# Controlador_de_velocidad_-_Placa_fuente.net
KiCad netlist of a schematic drawn in Altium Designer
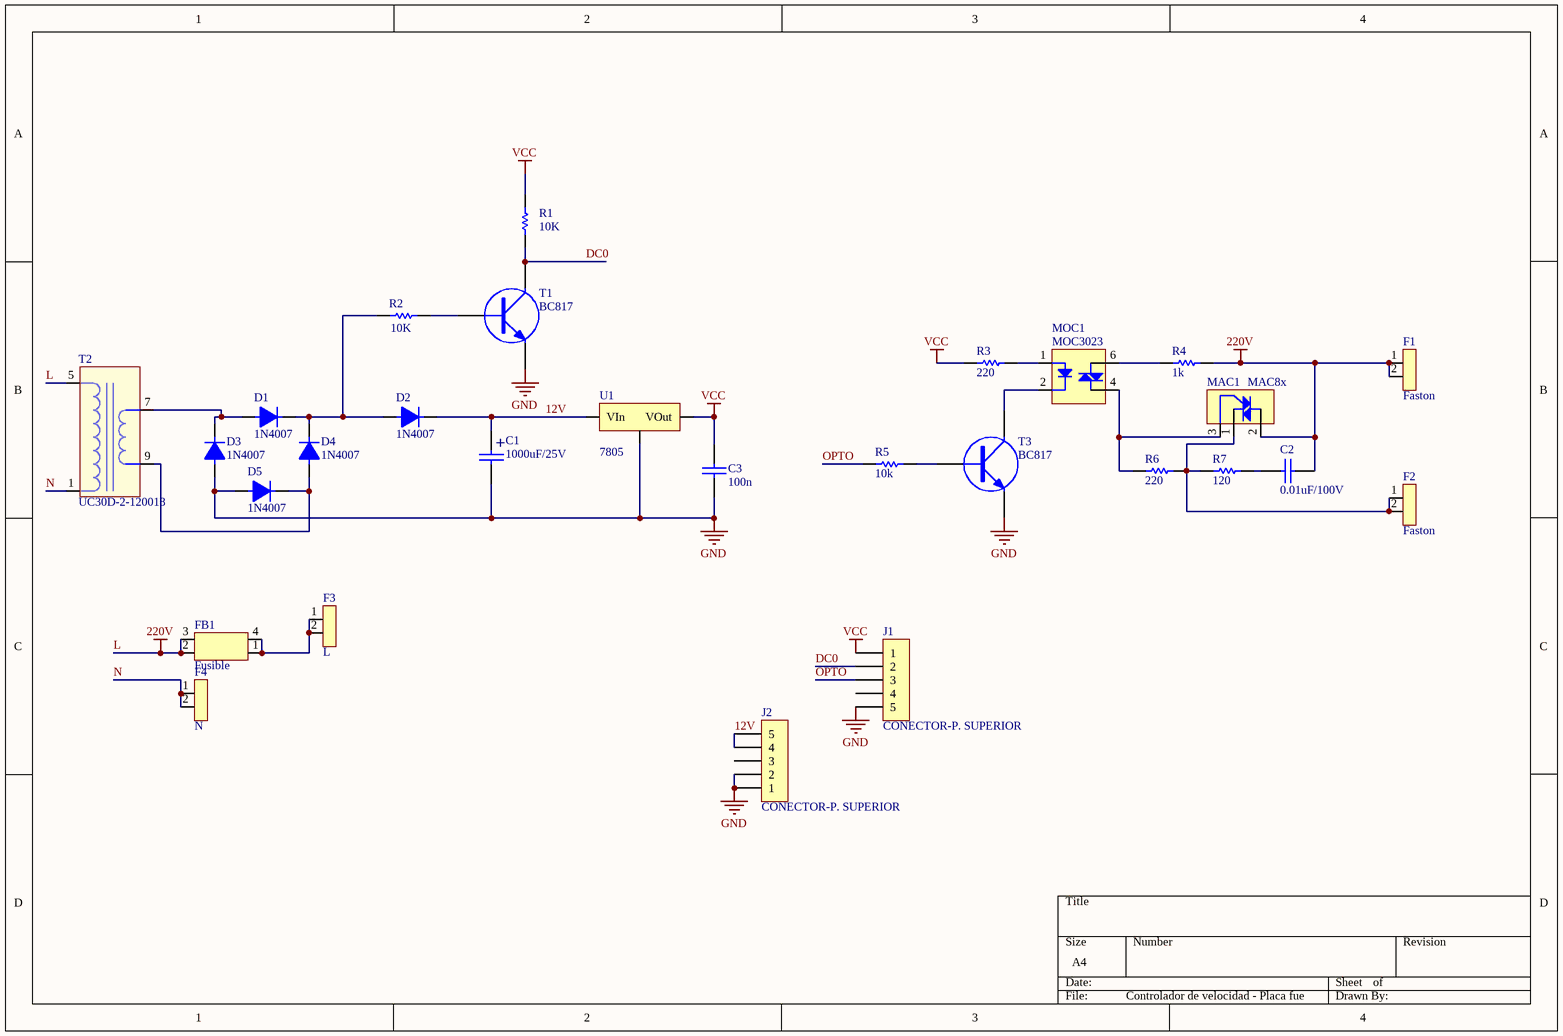
[diagram p0: Controlador de velocidad - Placa fuente.SchDoc]

(export (version "E")
  (design (tool "Eeschema 10.0.6"))
  (components
    (comp (ref "C1") (value "1000uF/25V") (footprint "CAP300RP") (libsource (lib "LIBPIOIX") (part "CAPPOL")))
    (comp (ref "C2") (value "0.01uF/100V") (footprint "CAP200") (libsource (lib "LIBPIOIX") (part "CAP")))
    (comp (ref "C3") (value "100n") (footprint "CAP200") (libsource (lib "LIBPIOIX") (part "CAP")))
    (comp (ref "D1") (value "1N4007") (footprint "DO41") (libsource (lib "LIBPIOIX") (part "DIODO")))
    (comp (ref "D2") (value "1N4007") (footprint "DO41") (libsource (lib "LIBPIOIX") (part "DIODO")))
    (comp (ref "D3") (value "1N4007") (footprint "DO41") (libsource (lib "LIBPIOIX") (part "DIODO")))
    (comp (ref "D4") (value "1N4007") (footprint "DO41") (libsource (lib "LIBPIOIX") (part "DIODO")))
    (comp (ref "D5") (value "1N4007") (footprint "DO41") (libsource (lib "LIBPIOIX") (part "DIODO")))
    (comp (ref "F1")
      (value "Faston")
      (footprint "Faston_V")
      (libsource (lib "Integrated_Library1") (part "FastonX1"))
    )
    (comp (ref "F2")
      (value "Faston")
      (footprint "Faston_V")
      (libsource (lib "Integrated_Library1") (part "FastonX1"))
    )
    (comp (ref "F3")
      (value "L")
      (footprint "Faston_V")
      (libsource (lib "Integrated_Library1") (part "FastonX1"))
    )
    (comp (ref "F4")
      (value "N")
      (footprint "Faston_V")
      (libsource (lib "Integrated_Library1") (part "FastonX1"))
    )
    (comp (ref "FB1")
      (value "Fusible")
      (footprint "Porta_fuse_2")
      (libsource (lib "Integrated_Library1") (part "Porta_fuse_1"))
    )
    (comp (ref "J1")
      (value "CONECTOR-P. SUPERIOR")
      (footprint "SIP5")
      (libsource (lib "LIBEBAL") (part "CON5"))
    )
    (comp (ref "J2") (value "CONECTOR-P. SUPERIOR") (footprint "SIP5") (libsource (lib "") (part "CON5_1")))
    (comp (ref "MAC1")
      (value "MAC8x")
      (footprint "TO-220_vert")
      (libsource (lib "Integrated_Library1") (part "MAC8x"))
    )
    (comp (ref "MOC1")
      (value "MOC3023")
      (footprint "4N33")
      (libsource (lib "Integrated_Library1") (part "MOC3023"))
    )
    (comp (ref "R1") (value "10K") (footprint "0805") (libsource (lib "LIBPIOIX") (part "RES")))
    (comp (ref "R2") (value "10K") (footprint "0805") (libsource (lib "LIBPIOIX") (part "RES")))
    (comp (ref "R3") (value "220") (footprint "0805") (libsource (lib "LIBPIOIX") (part "RES")))
    (comp (ref "R4") (value "1k") (footprint "RES300") (libsource (lib "LIBPIOIX") (part "RES")))
    (comp (ref "R5") (value "10k") (footprint "0805") (libsource (lib "LIBPIOIX") (part "RES")))
    (comp (ref "R6") (value "220") (footprint "RES300") (libsource (lib "LIBPIOIX") (part "RES")))
    (comp (ref "R7") (value "120") (footprint "RES400") (libsource (lib "LIBPIOIX") (part "RES")))
    (comp (ref "T1") (value "BC817") (footprint "SOT23") (libsource (lib "LIBPIOIX") (part "TRANSISTOR NPN")))
    (comp (ref "T2")
      (value "UC30D-2-120018")
      (footprint "Trafo_220_12_1")
      (libsource (lib "Integrated_Lib_1") (part "TRAFO_220_12_1"))
    )
    (comp (ref "T3") (value "BC817") (footprint "SOT23") (libsource (lib "LIBPIOIX") (part "TRANSISTOR NPN")))
    (comp (ref "U1")
      (value "7805")
      (footprint "TO-220 H")
      (description "REGULDOR POSITIVO")
      (libsource (lib "LIBPIOIX") (part "78XX"))
    )
  )
  (nets
    (net (code "1") (name "/12V") (class "Default")
      (node (ref "C1") (pin "1") (pinfunction "1_1") (pintype "passive"))
      (node (ref "D2") (pin "2") (pinfunction "2_2") (pintype "passive"))
      (node (ref "J2") (pin "4") (pinfunction "4_4") (pintype "passive"))
      (node (ref "J2") (pin "5") (pinfunction "5_5") (pintype "passive"))
      (node (ref "U1") (pin "1") (pinfunction "VIn_1") (pintype "passive"))
    )
    (net (code "2") (name "/DC0") (class "Default")
      (node (ref "J1") (pin "2") (pinfunction "2_2") (pintype "passive"))
      (node (ref "R1") (pin "1") (pinfunction "1_1") (pintype "passive"))
      (node (ref "T1") (pin "2") (pinfunction "C_2") (pintype "passive"))
    )
    (net (code "3") (name "/N") (class "Default")
      (node (ref "F4") (pin "1") (pintype "power_in"))
      (node (ref "F4") (pin "2") (pintype "power_in"))
      (node (ref "T2") (pin "1") (pinfunction "1_1") (pintype "passive"))
    )
    (net (code "4") (name "/OPTO") (class "Default")
      (node (ref "J1") (pin "3") (pinfunction "3_3") (pintype "passive"))
      (node (ref "R5") (pin "1") (pinfunction "1_1") (pintype "passive"))
    )
    (net (code "5") (name "220V") (class "Default")
      (node (ref "C2") (pin "1") (pinfunction "1_1") (pintype "passive"))
      (node (ref "F1") (pin "1") (pintype "power_in"))
      (node (ref "F1") (pin "2") (pintype "power_in"))
      (node (ref "FB1") (pin "2") (pintype "power_in"))
      (node (ref "FB1") (pin "3") (pintype "power_in"))
      (node (ref "MAC1") (pin "2") (pinfunction "MT2_2") (pintype "passive"))
      (node (ref "R4") (pin "1") (pinfunction "1_1") (pintype "passive"))
      (node (ref "T2") (pin "5") (pinfunction "5_5") (pintype "passive"))
    )
    (net (code "6") (name "GND") (class "Default")
      (node (ref "C1") (pin "2") (pinfunction "2_2") (pintype "passive"))
      (node (ref "C3") (pin "1") (pinfunction "1_1") (pintype "passive"))
      (node (ref "D3") (pin "1") (pinfunction "1_1") (pintype "passive"))
      (node (ref "D5") (pin "1") (pinfunction "1_1") (pintype "passive"))
      (node (ref "J1") (pin "5") (pinfunction "5_5") (pintype "passive"))
      (node (ref "J2") (pin "1") (pinfunction "1_1") (pintype "passive"))
      (node (ref "J2") (pin "2") (pinfunction "2_2") (pintype "passive"))
      (node (ref "T1") (pin "3") (pinfunction "E_3") (pintype "passive"))
      (node (ref "T3") (pin "3") (pinfunction "E_3") (pintype "passive"))
      (node (ref "U1") (pin "2") (pinfunction "GND_2") (pintype "passive"))
    )
    (net (code "7") (name "Net-(C2-Pad2)") (class "Default")
      (node (ref "C2") (pin "2") (pinfunction "2_2") (pintype "passive"))
      (node (ref "R7") (pin "1") (pinfunction "1_1") (pintype "passive"))
    )
    (net (code "8") (name "Net-(D1-Pad1)") (class "Default")
      (node (ref "D1") (pin "1") (pinfunction "1_1") (pintype "passive"))
      (node (ref "D3") (pin "2") (pinfunction "2_2") (pintype "passive"))
      (node (ref "T2") (pin "7") (pinfunction "7_7") (pintype "passive"))
    )
    (net (code "9") (name "Net-(D1-Pad2)") (class "Default")
      (node (ref "D1") (pin "2") (pinfunction "2_2") (pintype "passive"))
      (node (ref "D2") (pin "1") (pinfunction "1_1") (pintype "passive"))
      (node (ref "D4") (pin "2") (pinfunction "2_2") (pintype "passive"))
      (node (ref "R2") (pin "1") (pinfunction "1_1") (pintype "passive"))
    )
    (net (code "10") (name "Net-(D4-Pad1)") (class "Default")
      (node (ref "D4") (pin "1") (pinfunction "1_1") (pintype "passive"))
      (node (ref "D5") (pin "2") (pinfunction "2_2") (pintype "passive"))
      (node (ref "T2") (pin "9") (pinfunction "9_9") (pintype "passive"))
    )
    (net (code "11") (name "Net-(F3-Pad1)") (class "Default")
      (node (ref "F3") (pin "1") (pintype "power_in"))
      (node (ref "F3") (pin "2") (pintype "power_in"))
      (node (ref "FB1") (pin "1") (pintype "power_in"))
      (node (ref "FB1") (pin "4") (pintype "power_in"))
    )
    (net (code "12") (name "Net-(MAC1-G)") (class "Default")
      (node (ref "MAC1") (pin "3") (pinfunction "G_3") (pintype "passive"))
      (node (ref "MOC1") (pin "4") (pintype "passive"))
      (node (ref "R6") (pin "2") (pinfunction "2_2") (pintype "passive"))
    )
    (net (code "13") (name "Net-(MAC1-MT1)") (class "Default")
      (node (ref "F2") (pin "1") (pintype "power_in"))
      (node (ref "F2") (pin "2") (pintype "power_in"))
      (node (ref "MAC1") (pin "1") (pinfunction "MT1_1") (pintype "passive"))
      (node (ref "R6") (pin "1") (pinfunction "1_1") (pintype "passive"))
      (node (ref "R7") (pin "2") (pinfunction "2_2") (pintype "passive"))
    )
    (net (code "14") (name "Net-(MOC1-Pad1)") (class "Default")
      (node (ref "MOC1") (pin "1") (pintype "passive"))
      (node (ref "R3") (pin "1") (pinfunction "1_1") (pintype "passive"))
    )
    (net (code "15") (name "Net-(MOC1-Pad6)") (class "Default")
      (node (ref "MOC1") (pin "6") (pintype "passive"))
      (node (ref "R4") (pin "2") (pinfunction "2_2") (pintype "passive"))
    )
    (net (code "16") (name "Net-(T1-B)") (class "Default")
      (node (ref "R2") (pin "2") (pinfunction "2_2") (pintype "passive"))
      (node (ref "T1") (pin "1") (pinfunction "B_1") (pintype "passive"))
    )
    (net (code "17") (name "Net-(T3-B)") (class "Default")
      (node (ref "R5") (pin "2") (pinfunction "2_2") (pintype "passive"))
      (node (ref "T3") (pin "1") (pinfunction "B_1") (pintype "passive"))
    )
    (net (code "18") (name "Net-(T3-C)") (class "Default")
      (node (ref "MOC1") (pin "2") (pintype "passive"))
      (node (ref "T3") (pin "2") (pinfunction "C_2") (pintype "passive"))
    )
    (net (code "19") (name "VCC") (class "Default")
      (node (ref "C3") (pin "2") (pinfunction "2_2") (pintype "passive"))
      (node (ref "J1") (pin "1") (pinfunction "1_1") (pintype "passive"))
      (node (ref "R1") (pin "2") (pinfunction "2_2") (pintype "passive"))
      (node (ref "R3") (pin "2") (pinfunction "2_2") (pintype "passive"))
      (node (ref "U1") (pin "3") (pinfunction "VOut_3") (pintype "passive"))
    )
    (net (code "20") (name "unconnected-(J1-Pad4)") (class "Default")
      (node (ref "J1") (pin "4") (pinfunction "4_4") (pintype "passive"))
    )
    (net (code "21") (name "unconnected-(J2-Pad3)") (class "Default")
      (node (ref "J2") (pin "3") (pinfunction "3_3") (pintype "passive"))
    )
  )
)
